# WirlessSubSystem.net
KiCad netlist of a schematic drawn in Altium Designer
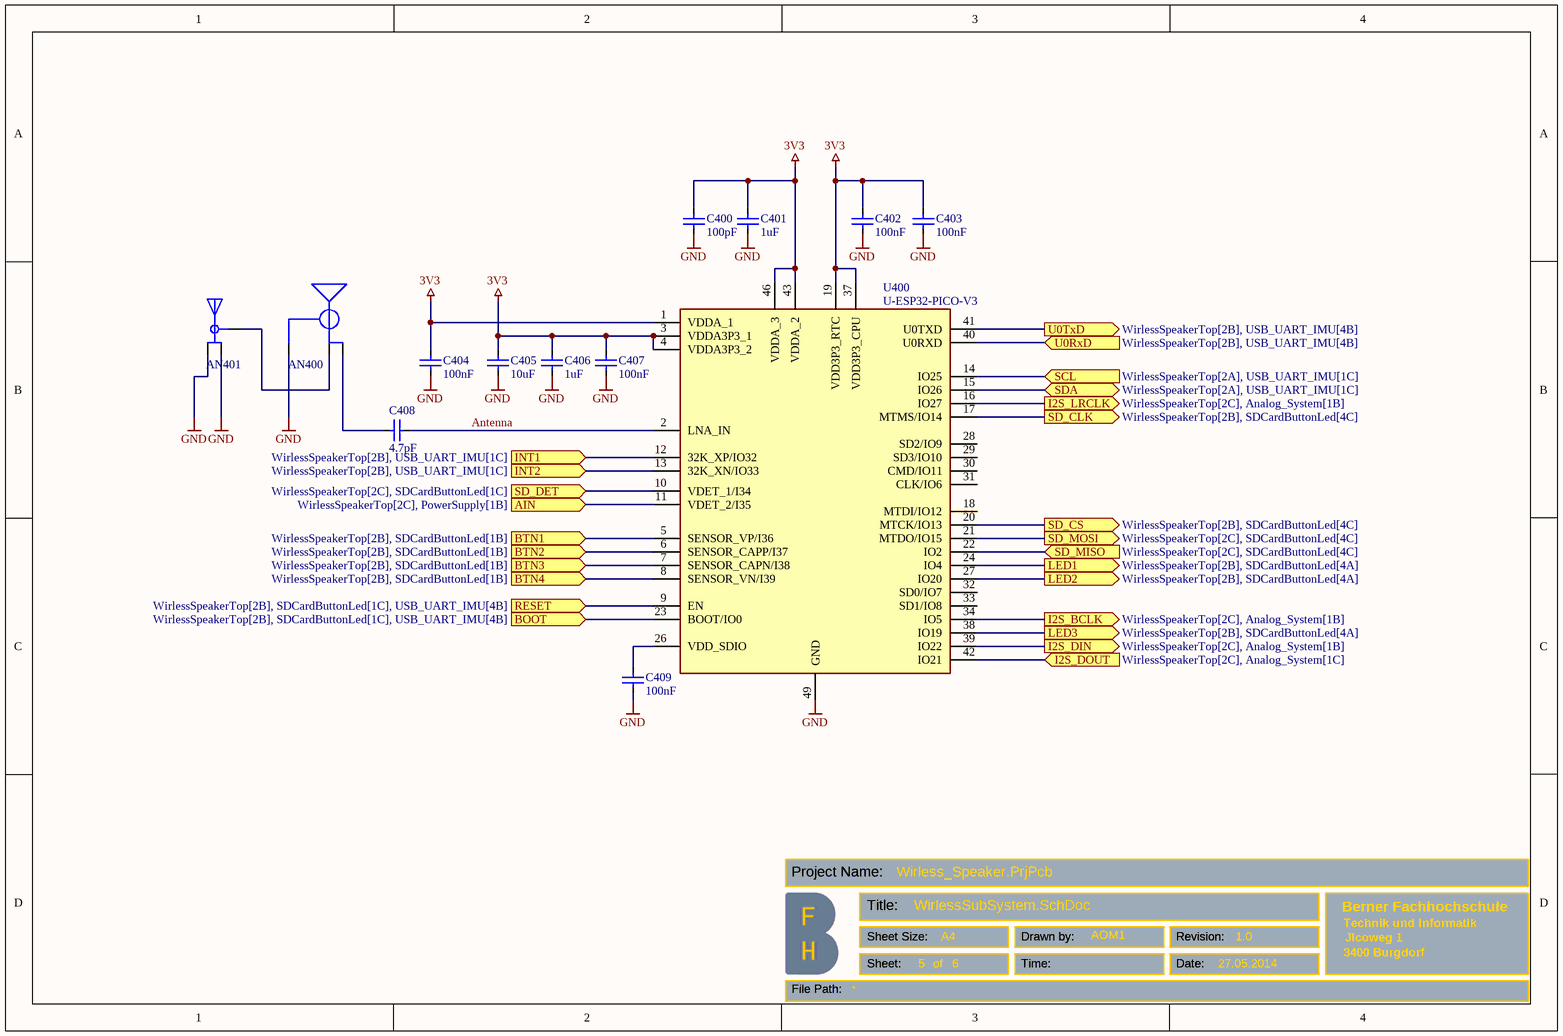
[diagram p0: WirlessSubSystem.SchDoc]

(export (version "E")
  (design (tool "Eeschema 10.0.6"))
  (components
    (comp (ref "AN400")
      (value "PCB-Antenna")
      (footprint "ESP32-PCB-Antenna")
      (description "PCB, 2.4 GHz Antenna")
      (fields (field (name "MANUFACTURER") "BFH"))
      (libsource (lib "WirelessAudioSpeaker") (part "AN-ESP32-PCB-Antenna"))
    )
    (comp (ref "AN401")
      (value "AN-U.FL-R-SMT-1(10)")
      (footprint "HRS_U.FL-R-SMT-1(10)")
      (description "U.FL _UMCC_ Connector Receptacle, Male Pin 50Ohm Surface Mount Solder")
      (fields (field (name "MFR. PART NO.") "U.FL-R-SMT-1(10)") (field (name "MANUFACTURER") "Hirose"))
      (libsource (lib "WirelessAudioSpeaker") (part "AN-U.FL-R-SMT-1(10)"))
    )
    (comp (ref "C400")
      (value "100pF")
      (footprint "C-0603")
      (description "Multilayer Ceramic Capacitors MLCC")
      (fields (field (name "MANUFACTURER") "Murata Electronics") (field (name "MFR. PART NO.") "GRM18..."))
      (libsource (lib "WirelessAudioSpeaker") (part "C-SMD-0603"))
    )
    (comp (ref "C401")
      (value "1uF")
      (footprint "C-0603")
      (description "Multilayer Ceramic Capacitors MLCC")
      (fields (field (name "MANUFACTURER") "Murata Electronics") (field (name "MFR. PART NO.") "GRM18..."))
      (libsource (lib "WirelessAudioSpeaker") (part "C-SMD-0603"))
    )
    (comp (ref "C402")
      (value "100nF")
      (footprint "C-0603")
      (description "Multilayer Ceramic Capacitors MLCC")
      (fields (field (name "MANUFACTURER") "Murata Electronics") (field (name "MFR. PART NO.") "GRM18..."))
      (libsource (lib "WirelessAudioSpeaker") (part "C-SMD-0603"))
    )
    (comp (ref "C403")
      (value "100nF")
      (footprint "C-0603")
      (description "Multilayer Ceramic Capacitors MLCC")
      (fields (field (name "MANUFACTURER") "Murata Electronics") (field (name "MFR. PART NO.") "GRM18..."))
      (libsource (lib "WirelessAudioSpeaker") (part "C-SMD-0603"))
    )
    (comp (ref "C404")
      (value "100nF")
      (footprint "C-0603")
      (description "Multilayer Ceramic Capacitors MLCC")
      (fields (field (name "MANUFACTURER") "Murata Electronics") (field (name "MFR. PART NO.") "GRM18..."))
      (libsource (lib "WirelessAudioSpeaker") (part "C-SMD-0603"))
    )
    (comp (ref "C405")
      (value "10uF")
      (footprint "C-0603")
      (description "Multilayer Ceramic Capacitors MLCC")
      (fields (field (name "MANUFACTURER") "Murata Electronics") (field (name "MFR. PART NO.") "GRM18..."))
      (libsource (lib "WirelessAudioSpeaker") (part "C-SMD-0603"))
    )
    (comp (ref "C406")
      (value "1uF")
      (footprint "C-0603")
      (description "Multilayer Ceramic Capacitors MLCC")
      (fields (field (name "MANUFACTURER") "Murata Electronics") (field (name "MFR. PART NO.") "GRM18..."))
      (libsource (lib "WirelessAudioSpeaker") (part "C-SMD-0603"))
    )
    (comp (ref "C407")
      (value "100nF")
      (footprint "C-0603")
      (description "Multilayer Ceramic Capacitors MLCC")
      (fields (field (name "MANUFACTURER") "Murata Electronics") (field (name "MFR. PART NO.") "GRM18..."))
      (libsource (lib "WirelessAudioSpeaker") (part "C-SMD-0603"))
    )
    (comp (ref "C408")
      (value "4.7pF")
      (footprint "C-0402")
      (description "Multilayer Ceramic Capacitors MLCC")
      (fields (field (name "MANUFACTURER") "Murata Electronics") (field (name "MFR. PART NO.") "GRM02*"))
      (libsource (lib "WirelessAudioSpeaker") (part "C-SMD-0402"))
    )
    (comp (ref "C409")
      (value "100nF")
      (footprint "C-0603")
      (description "Multilayer Ceramic Capacitors MLCC")
      (fields (field (name "MANUFACTURER") "Murata Electronics") (field (name "MFR. PART NO.") "GRM18..."))
      (libsource (lib "WirelessAudioSpeaker") (part "C-SMD-0603"))
    )
    (comp (ref "U400")
      (value "U-ESP32-PICO-V3")
      (footprint "ESP32PICOV3")
      (description "RF System on a Chip")
      (fields
        (field (name "MANUFACTURER_PART_NUMBER") "ESP32-PICO-V3")
        (field (name "MOUSER PART NUMBER") "356-ESP32-PICO-V3")
      )
      (libsource (lib "WirelessAudioSpeaker") (part "U-ESP32-PICO-V3-BFH"))
    )
  )
  (nets
    (net (code "1") (name "/AIN") (class "Default")
      (node (ref "U400") (pin "11") (pinfunction "VDET_2/I35_11") (pintype "passive"))
    )
    (net (code "2") (name "/Antenna") (class "Default")
      (node (ref "C408") (pin "1") (pinfunction "1_1") (pintype "passive"))
      (node (ref "U400") (pin "2") (pinfunction "LNA_IN_2") (pintype "passive"))
    )
    (net (code "3") (name "/BOOT") (class "Default")
      (node (ref "U400") (pin "23") (pinfunction "BOOT/IO0_23") (pintype "passive"))
    )
    (net (code "4") (name "/BTN1") (class "Default")
      (node (ref "U400") (pin "5") (pinfunction "SENSOR_VP/I36_5") (pintype "passive"))
    )
    (net (code "5") (name "/BTN2") (class "Default")
      (node (ref "U400") (pin "6") (pinfunction "SENSOR_CAPP/I37_6") (pintype "passive"))
    )
    (net (code "6") (name "/BTN3") (class "Default")
      (node (ref "U400") (pin "7") (pinfunction "SENSOR_CAPN/I38_7") (pintype "passive"))
    )
    (net (code "7") (name "/BTN4") (class "Default")
      (node (ref "U400") (pin "8") (pinfunction "SENSOR_VN/I39_8") (pintype "passive"))
    )
    (net (code "8") (name "/I2S_BCLK") (class "Default")
      (node (ref "U400") (pin "34") (pinfunction "IO5_34") (pintype "passive"))
    )
    (net (code "9") (name "/I2S_DIN") (class "Default")
      (node (ref "U400") (pin "39") (pinfunction "IO22_39") (pintype "passive"))
    )
    (net (code "10") (name "/I2S_DOUT") (class "Default")
      (node (ref "U400") (pin "42") (pinfunction "IO21_42") (pintype "passive"))
    )
    (net (code "11") (name "/I2S_LRCLK") (class "Default")
      (node (ref "U400") (pin "16") (pinfunction "IO27_16") (pintype "passive"))
    )
    (net (code "12") (name "/INT1") (class "Default")
      (node (ref "U400") (pin "12") (pinfunction "32K_XP/IO32_12") (pintype "passive"))
    )
    (net (code "13") (name "/INT2") (class "Default")
      (node (ref "U400") (pin "13") (pinfunction "32K_XN/IO33_13") (pintype "passive"))
    )
    (net (code "14") (name "/LED1") (class "Default")
      (node (ref "U400") (pin "24") (pinfunction "IO4_24") (pintype "passive"))
    )
    (net (code "15") (name "/LED2") (class "Default")
      (node (ref "U400") (pin "27") (pinfunction "IO20_27") (pintype "passive"))
    )
    (net (code "16") (name "/LED3") (class "Default")
      (node (ref "U400") (pin "38") (pinfunction "IO19_38") (pintype "passive"))
    )
    (net (code "17") (name "/RESET") (class "Default")
      (node (ref "U400") (pin "9") (pinfunction "EN_9") (pintype "passive"))
    )
    (net (code "18") (name "/SCL") (class "Default")
      (node (ref "U400") (pin "14") (pinfunction "IO25_14") (pintype "passive"))
    )
    (net (code "19") (name "/SDA") (class "Default")
      (node (ref "U400") (pin "15") (pinfunction "IO26_15") (pintype "passive"))
    )
    (net (code "20") (name "/SD_CLK") (class "Default")
      (node (ref "U400") (pin "17") (pinfunction "MTMS/IO14_17") (pintype "passive"))
    )
    (net (code "21") (name "/SD_CS") (class "Default")
      (node (ref "U400") (pin "20") (pinfunction "MTCK/IO13_20") (pintype "passive"))
    )
    (net (code "22") (name "/SD_DET") (class "Default")
      (node (ref "U400") (pin "10") (pinfunction "VDET_1/I34_10") (pintype "passive"))
    )
    (net (code "23") (name "/SD_MISO") (class "Default")
      (node (ref "U400") (pin "22") (pinfunction "IO2_22") (pintype "passive"))
    )
    (net (code "24") (name "/SD_MOSI") (class "Default")
      (node (ref "U400") (pin "21") (pinfunction "MTDO/IO15_21") (pintype "passive"))
    )
    (net (code "25") (name "/U0RxD") (class "Default")
      (node (ref "U400") (pin "40") (pinfunction "U0RXD_40") (pintype "passive"))
    )
    (net (code "26") (name "/U0TxD") (class "Default")
      (node (ref "U400") (pin "41") (pinfunction "U0TXD_41") (pintype "passive"))
    )
    (net (code "27") (name "3V3") (class "Default")
      (node (ref "C400") (pin "2") (pinfunction "2_2") (pintype "passive"))
      (node (ref "C401") (pin "2") (pinfunction "2_2") (pintype "passive"))
      (node (ref "C402") (pin "2") (pinfunction "2_2") (pintype "passive"))
      (node (ref "C403") (pin "2") (pinfunction "2_2") (pintype "passive"))
      (node (ref "C404") (pin "2") (pinfunction "2_2") (pintype "passive"))
      (node (ref "C405") (pin "2") (pinfunction "2_2") (pintype "passive"))
      (node (ref "C406") (pin "2") (pinfunction "2_2") (pintype "passive"))
      (node (ref "C407") (pin "2") (pinfunction "2_2") (pintype "passive"))
      (node (ref "U400") (pin "1") (pinfunction "VDDA_1_1") (pintype "passive"))
      (node (ref "U400") (pin "19") (pinfunction "VDD3P3_RTC_19") (pintype "passive"))
      (node (ref "U400") (pin "3") (pinfunction "VDDA3P3_1_3") (pintype "passive"))
      (node (ref "U400") (pin "37") (pinfunction "VDD3P3_CPU_37") (pintype "passive"))
      (node (ref "U400") (pin "4") (pinfunction "VDDA3P3_2_4") (pintype "passive"))
      (node (ref "U400") (pin "43") (pinfunction "VDDA_2_43") (pintype "passive"))
      (node (ref "U400") (pin "46") (pinfunction "VDDA_3_46") (pintype "passive"))
    )
    (net (code "28") (name "GND") (class "Default")
      (node (ref "AN400") (pin "GND") (pintype "passive"))
      (node (ref "AN401") (pin "1") (pinfunction "GND_1") (pintype "passive"))
      (node (ref "AN401") (pin "3") (pinfunction "GND_3") (pintype "passive"))
      (node (ref "C400") (pin "1") (pinfunction "1_1") (pintype "passive"))
      (node (ref "C401") (pin "1") (pinfunction "1_1") (pintype "passive"))
      (node (ref "C402") (pin "1") (pinfunction "1_1") (pintype "passive"))
      (node (ref "C403") (pin "1") (pinfunction "1_1") (pintype "passive"))
      (node (ref "C404") (pin "1") (pinfunction "1_1") (pintype "passive"))
      (node (ref "C405") (pin "1") (pinfunction "1_1") (pintype "passive"))
      (node (ref "C406") (pin "1") (pinfunction "1_1") (pintype "passive"))
      (node (ref "C407") (pin "1") (pinfunction "1_1") (pintype "passive"))
      (node (ref "C409") (pin "2") (pinfunction "2_2") (pintype "passive"))
      (node (ref "U400") (pin "49") (pinfunction "GND_49") (pintype "passive"))
    )
    (net (code "29") (name "Net-(AN400-ANT-PadANT1)") (class "Default")
      (node (ref "AN400") (pin "ANT1") (pinfunction "ANT_ANT1") (pintype "passive"))
      (node (ref "C408") (pin "2") (pinfunction "2_2") (pintype "passive"))
    )
    (net (code "30") (name "Net-(AN401-SIG)") (class "Default")
      (node (ref "AN400") (pin "ANT2") (pinfunction "ANT_ANT2") (pintype "passive"))
      (node (ref "AN401") (pin "2") (pinfunction "SIG_2") (pintype "passive"))
    )
    (net (code "31") (name "Net-(U400-VDD_SDIO)") (class "Default")
      (node (ref "C409") (pin "1") (pinfunction "1_1") (pintype "passive"))
      (node (ref "U400") (pin "26") (pinfunction "VDD_SDIO_26") (pintype "passive"))
    )
    (net (code "32") (name "unconnected-(U400-CLK{slash}IO6-Pad31)") (class "Default")
      (node (ref "U400") (pin "31") (pinfunction "CLK/IO6_31") (pintype "passive"))
    )
    (net (code "33") (name "unconnected-(U400-CMD{slash}IO11-Pad30)") (class "Default")
      (node (ref "U400") (pin "30") (pinfunction "CMD/IO11_30") (pintype "passive"))
    )
    (net (code "34") (name "unconnected-(U400-MTDI{slash}IO12-Pad18)") (class "Default")
      (node (ref "U400") (pin "18") (pinfunction "MTDI/IO12_18") (pintype "passive"))
    )
    (net (code "35") (name "unconnected-(U400-SD0{slash}IO7-Pad32)") (class "Default")
      (node (ref "U400") (pin "32") (pinfunction "SD0/IO7_32") (pintype "passive"))
    )
    (net (code "36") (name "unconnected-(U400-SD1{slash}IO8-Pad33)") (class "Default")
      (node (ref "U400") (pin "33") (pinfunction "SD1/IO8_33") (pintype "passive"))
    )
    (net (code "37") (name "unconnected-(U400-SD2{slash}IO9-Pad28)") (class "Default")
      (node (ref "U400") (pin "28") (pinfunction "SD2/IO9_28") (pintype "passive"))
    )
    (net (code "38") (name "unconnected-(U400-SD3{slash}IO10-Pad29)") (class "Default")
      (node (ref "U400") (pin "29") (pinfunction "SD3/IO10_29") (pintype "passive"))
    )
  )
)
